# PatchBay.net
KiCad netlist of a schematic drawn in EAGLE
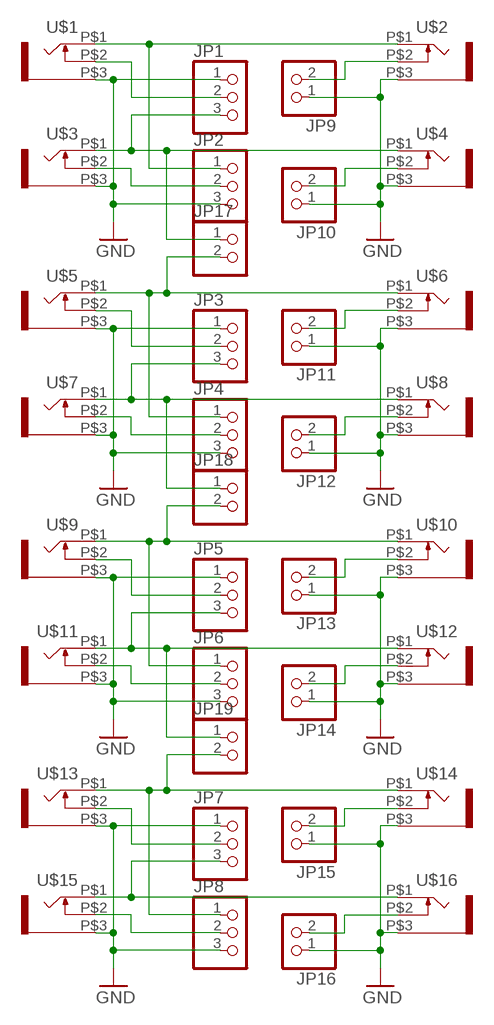
[diagram p0: schematic, sheet 1]

(export (version "E")
  (design (tool "Eeschema 10.0.6"))
  (components
    (comp (ref "JP1")
      (value "PINHD-1X3")
      (footprint "eagle-import:1X03")
      (libsource (lib "eagle-import") (part "PINHD-1X3"))
    )
    (comp (ref "JP2")
      (value "PINHD-1X3")
      (footprint "eagle-import:1X03")
      (libsource (lib "eagle-import") (part "PINHD-1X3"))
    )
    (comp (ref "JP3")
      (value "PINHD-1X3")
      (footprint "eagle-import:1X03")
      (libsource (lib "eagle-import") (part "PINHD-1X3"))
    )
    (comp (ref "JP4")
      (value "PINHD-1X3")
      (footprint "eagle-import:1X03")
      (libsource (lib "eagle-import") (part "PINHD-1X3"))
    )
    (comp (ref "JP5")
      (value "PINHD-1X3")
      (footprint "eagle-import:1X03")
      (libsource (lib "eagle-import") (part "PINHD-1X3"))
    )
    (comp (ref "JP6")
      (value "PINHD-1X3")
      (footprint "eagle-import:1X03")
      (libsource (lib "eagle-import") (part "PINHD-1X3"))
    )
    (comp (ref "JP7")
      (value "PINHD-1X3")
      (footprint "eagle-import:1X03")
      (libsource (lib "eagle-import") (part "PINHD-1X3"))
    )
    (comp (ref "JP8")
      (value "PINHD-1X3")
      (footprint "eagle-import:1X03")
      (libsource (lib "eagle-import") (part "PINHD-1X3"))
    )
    (comp (ref "JP9")
      (value "PINHD-1X2")
      (footprint "eagle-import:1X02")
      (libsource (lib "eagle-import") (part "PINHD-1X2"))
    )
    (comp (ref "JP10")
      (value "PINHD-1X2")
      (footprint "eagle-import:1X02")
      (libsource (lib "eagle-import") (part "PINHD-1X2"))
    )
    (comp (ref "JP11")
      (value "PINHD-1X2")
      (footprint "eagle-import:1X02")
      (libsource (lib "eagle-import") (part "PINHD-1X2"))
    )
    (comp (ref "JP12")
      (value "PINHD-1X2")
      (footprint "eagle-import:1X02")
      (libsource (lib "eagle-import") (part "PINHD-1X2"))
    )
    (comp (ref "JP13")
      (value "PINHD-1X2")
      (footprint "eagle-import:1X02")
      (libsource (lib "eagle-import") (part "PINHD-1X2"))
    )
    (comp (ref "JP14")
      (value "PINHD-1X2")
      (footprint "eagle-import:1X02")
      (libsource (lib "eagle-import") (part "PINHD-1X2"))
    )
    (comp (ref "JP15")
      (value "PINHD-1X2")
      (footprint "eagle-import:1X02")
      (libsource (lib "eagle-import") (part "PINHD-1X2"))
    )
    (comp (ref "JP16")
      (value "PINHD-1X2")
      (footprint "eagle-import:1X02")
      (libsource (lib "eagle-import") (part "PINHD-1X2"))
    )
    (comp (ref "JP17")
      (value "PINHD-1X2")
      (footprint "eagle-import:1X02")
      (libsource (lib "eagle-import") (part "PINHD-1X2"))
    )
    (comp (ref "JP18")
      (value "PINHD-1X2")
      (footprint "eagle-import:1X02")
      (libsource (lib "eagle-import") (part "PINHD-1X2"))
    )
    (comp (ref "JP19")
      (value "PINHD-1X2")
      (footprint "eagle-import:1X02")
      (libsource (lib "eagle-import") (part "PINHD-1X2"))
    )
    (comp (ref "U$1")
      (value "JACK-UJ-3502-R")
      (footprint "eagle-import:UJ-3502-R")
      (libsource (lib "eagle-import") (part "JACK-UJ-3502-R"))
    )
    (comp (ref "U$2")
      (value "JACK-UJ-3502-R")
      (footprint "eagle-import:UJ-3502-R")
      (libsource (lib "eagle-import") (part "JACK-UJ-3502-R"))
    )
    (comp (ref "U$3")
      (value "JACK-UJ-3502-R")
      (footprint "eagle-import:UJ-3502-R")
      (libsource (lib "eagle-import") (part "JACK-UJ-3502-R"))
    )
    (comp (ref "U$4")
      (value "JACK-UJ-3502-R")
      (footprint "eagle-import:UJ-3502-R")
      (libsource (lib "eagle-import") (part "JACK-UJ-3502-R"))
    )
    (comp (ref "U$5")
      (value "JACK-UJ-3502-R")
      (footprint "eagle-import:UJ-3502-R")
      (libsource (lib "eagle-import") (part "JACK-UJ-3502-R"))
    )
    (comp (ref "U$6")
      (value "JACK-UJ-3502-R")
      (footprint "eagle-import:UJ-3502-R")
      (libsource (lib "eagle-import") (part "JACK-UJ-3502-R"))
    )
    (comp (ref "U$7")
      (value "JACK-UJ-3502-R")
      (footprint "eagle-import:UJ-3502-R")
      (libsource (lib "eagle-import") (part "JACK-UJ-3502-R"))
    )
    (comp (ref "U$8")
      (value "JACK-UJ-3502-R")
      (footprint "eagle-import:UJ-3502-R")
      (libsource (lib "eagle-import") (part "JACK-UJ-3502-R"))
    )
    (comp (ref "U$9")
      (value "JACK-UJ-3502-R")
      (footprint "eagle-import:UJ-3502-R")
      (libsource (lib "eagle-import") (part "JACK-UJ-3502-R"))
    )
    (comp (ref "U$10")
      (value "JACK-UJ-3502-R")
      (footprint "eagle-import:UJ-3502-R")
      (libsource (lib "eagle-import") (part "JACK-UJ-3502-R"))
    )
    (comp (ref "U$11")
      (value "JACK-UJ-3502-R")
      (footprint "eagle-import:UJ-3502-R")
      (libsource (lib "eagle-import") (part "JACK-UJ-3502-R"))
    )
    (comp (ref "U$12")
      (value "JACK-UJ-3502-R")
      (footprint "eagle-import:UJ-3502-R")
      (libsource (lib "eagle-import") (part "JACK-UJ-3502-R"))
    )
    (comp (ref "U$13")
      (value "JACK-UJ-3502-R")
      (footprint "eagle-import:UJ-3502-R")
      (libsource (lib "eagle-import") (part "JACK-UJ-3502-R"))
    )
    (comp (ref "U$14")
      (value "JACK-UJ-3502-R")
      (footprint "eagle-import:UJ-3502-R")
      (libsource (lib "eagle-import") (part "JACK-UJ-3502-R"))
    )
    (comp (ref "U$15")
      (value "JACK-UJ-3502-R")
      (footprint "eagle-import:UJ-3502-R")
      (libsource (lib "eagle-import") (part "JACK-UJ-3502-R"))
    )
    (comp (ref "U$16")
      (value "JACK-UJ-3502-R")
      (footprint "eagle-import:UJ-3502-R")
      (libsource (lib "eagle-import") (part "JACK-UJ-3502-R"))
    )
  )
  (nets
    (net (code "1") (name "GND") (class "Default")
      (node (ref "JP1") (pin "1") (pinfunction "1_1") (pintype "passive"))
      (node (ref "JP10") (pin "1") (pinfunction "1_1") (pintype "passive"))
      (node (ref "JP11") (pin "1") (pinfunction "1_1") (pintype "passive"))
      (node (ref "JP12") (pin "1") (pinfunction "1_1") (pintype "passive"))
      (node (ref "JP13") (pin "1") (pinfunction "1_1") (pintype "passive"))
      (node (ref "JP14") (pin "1") (pinfunction "1_1") (pintype "passive"))
      (node (ref "JP15") (pin "1") (pinfunction "1_1") (pintype "passive"))
      (node (ref "JP16") (pin "1") (pinfunction "1_1") (pintype "passive"))
      (node (ref "JP2") (pin "3") (pinfunction "3_3") (pintype "passive"))
      (node (ref "JP3") (pin "1") (pinfunction "1_1") (pintype "passive"))
      (node (ref "JP4") (pin "3") (pinfunction "3_3") (pintype "passive"))
      (node (ref "JP5") (pin "1") (pinfunction "1_1") (pintype "passive"))
      (node (ref "JP6") (pin "3") (pinfunction "3_3") (pintype "passive"))
      (node (ref "JP7") (pin "1") (pinfunction "1_1") (pintype "passive"))
      (node (ref "JP8") (pin "3") (pinfunction "3_3") (pintype "passive"))
      (node (ref "JP9") (pin "1") (pinfunction "1_1") (pintype "passive"))
      (node (ref "U$1") (pin "P$3") (pinfunction "SLEEVE_P$3") (pintype "passive"))
      (node (ref "U$10") (pin "P$3") (pinfunction "SLEEVE_P$3") (pintype "passive"))
      (node (ref "U$11") (pin "P$3") (pinfunction "SLEEVE_P$3") (pintype "passive"))
      (node (ref "U$12") (pin "P$3") (pinfunction "SLEEVE_P$3") (pintype "passive"))
      (node (ref "U$13") (pin "P$3") (pinfunction "SLEEVE_P$3") (pintype "passive"))
      (node (ref "U$14") (pin "P$3") (pinfunction "SLEEVE_P$3") (pintype "passive"))
      (node (ref "U$15") (pin "P$3") (pinfunction "SLEEVE_P$3") (pintype "passive"))
      (node (ref "U$16") (pin "P$3") (pinfunction "SLEEVE_P$3") (pintype "passive"))
      (node (ref "U$2") (pin "P$3") (pinfunction "SLEEVE_P$3") (pintype "passive"))
      (node (ref "U$3") (pin "P$3") (pinfunction "SLEEVE_P$3") (pintype "passive"))
      (node (ref "U$4") (pin "P$3") (pinfunction "SLEEVE_P$3") (pintype "passive"))
      (node (ref "U$5") (pin "P$3") (pinfunction "SLEEVE_P$3") (pintype "passive"))
      (node (ref "U$6") (pin "P$3") (pinfunction "SLEEVE_P$3") (pintype "passive"))
      (node (ref "U$7") (pin "P$3") (pinfunction "SLEEVE_P$3") (pintype "passive"))
      (node (ref "U$8") (pin "P$3") (pinfunction "SLEEVE_P$3") (pintype "passive"))
      (node (ref "U$9") (pin "P$3") (pinfunction "SLEEVE_P$3") (pintype "passive"))
    )
    (net (code "2") (name "Net-(U$1-SW)") (class "Default")
      (node (ref "JP1") (pin "2") (pinfunction "2_2") (pintype "passive"))
      (node (ref "U$1") (pin "P$2") (pinfunction "SW_P$2") (pintype "passive"))
    )
    (net (code "3") (name "Net-(U$1-TIP)") (class "Default")
      (node (ref "JP2") (pin "1") (pinfunction "1_1") (pintype "passive"))
      (node (ref "U$1") (pin "P$1") (pinfunction "TIP_P$1") (pintype "passive"))
      (node (ref "U$2") (pin "P$1") (pinfunction "TIP_P$1") (pintype "passive"))
    )
    (net (code "4") (name "Net-(U$2-SW)") (class "Default")
      (node (ref "JP9") (pin "2") (pinfunction "2_2") (pintype "passive"))
      (node (ref "U$2") (pin "P$2") (pinfunction "SW_P$2") (pintype "passive"))
    )
    (net (code "5") (name "Net-(U$3-SW)") (class "Default")
      (node (ref "JP2") (pin "2") (pinfunction "2_2") (pintype "passive"))
      (node (ref "U$3") (pin "P$2") (pinfunction "SW_P$2") (pintype "passive"))
    )
    (net (code "6") (name "Net-(U$3-TIP)") (class "Default")
      (node (ref "JP1") (pin "3") (pinfunction "3_3") (pintype "passive"))
      (node (ref "JP17") (pin "1") (pinfunction "1_1") (pintype "passive"))
      (node (ref "U$3") (pin "P$1") (pinfunction "TIP_P$1") (pintype "passive"))
      (node (ref "U$4") (pin "P$1") (pinfunction "TIP_P$1") (pintype "passive"))
    )
    (net (code "7") (name "Net-(U$4-SW)") (class "Default")
      (node (ref "JP10") (pin "2") (pinfunction "2_2") (pintype "passive"))
      (node (ref "U$4") (pin "P$2") (pinfunction "SW_P$2") (pintype "passive"))
    )
    (net (code "8") (name "Net-(U$5-SW)") (class "Default")
      (node (ref "JP3") (pin "2") (pinfunction "2_2") (pintype "passive"))
      (node (ref "U$5") (pin "P$2") (pinfunction "SW_P$2") (pintype "passive"))
    )
    (net (code "9") (name "Net-(U$5-TIP)") (class "Default")
      (node (ref "JP17") (pin "2") (pinfunction "2_2") (pintype "passive"))
      (node (ref "JP4") (pin "1") (pinfunction "1_1") (pintype "passive"))
      (node (ref "U$5") (pin "P$1") (pinfunction "TIP_P$1") (pintype "passive"))
      (node (ref "U$6") (pin "P$1") (pinfunction "TIP_P$1") (pintype "passive"))
    )
    (net (code "10") (name "Net-(U$6-SW)") (class "Default")
      (node (ref "JP11") (pin "2") (pinfunction "2_2") (pintype "passive"))
      (node (ref "U$6") (pin "P$2") (pinfunction "SW_P$2") (pintype "passive"))
    )
    (net (code "11") (name "Net-(U$7-SW)") (class "Default")
      (node (ref "JP4") (pin "2") (pinfunction "2_2") (pintype "passive"))
      (node (ref "U$7") (pin "P$2") (pinfunction "SW_P$2") (pintype "passive"))
    )
    (net (code "12") (name "Net-(U$7-TIP)") (class "Default")
      (node (ref "JP18") (pin "1") (pinfunction "1_1") (pintype "passive"))
      (node (ref "JP3") (pin "3") (pinfunction "3_3") (pintype "passive"))
      (node (ref "U$7") (pin "P$1") (pinfunction "TIP_P$1") (pintype "passive"))
      (node (ref "U$8") (pin "P$1") (pinfunction "TIP_P$1") (pintype "passive"))
    )
    (net (code "13") (name "Net-(U$8-SW)") (class "Default")
      (node (ref "JP12") (pin "2") (pinfunction "2_2") (pintype "passive"))
      (node (ref "U$8") (pin "P$2") (pinfunction "SW_P$2") (pintype "passive"))
    )
    (net (code "14") (name "Net-(U$9-SW)") (class "Default")
      (node (ref "JP5") (pin "2") (pinfunction "2_2") (pintype "passive"))
      (node (ref "U$9") (pin "P$2") (pinfunction "SW_P$2") (pintype "passive"))
    )
    (net (code "15") (name "Net-(U$10-SW)") (class "Default")
      (node (ref "JP13") (pin "2") (pinfunction "2_2") (pintype "passive"))
      (node (ref "U$10") (pin "P$2") (pinfunction "SW_P$2") (pintype "passive"))
    )
    (net (code "16") (name "Net-(U$10-TIP)") (class "Default")
      (node (ref "JP18") (pin "2") (pinfunction "2_2") (pintype "passive"))
      (node (ref "JP6") (pin "1") (pinfunction "1_1") (pintype "passive"))
      (node (ref "U$10") (pin "P$1") (pinfunction "TIP_P$1") (pintype "passive"))
      (node (ref "U$9") (pin "P$1") (pinfunction "TIP_P$1") (pintype "passive"))
    )
    (net (code "17") (name "Net-(U$11-SW)") (class "Default")
      (node (ref "JP6") (pin "2") (pinfunction "2_2") (pintype "passive"))
      (node (ref "U$11") (pin "P$2") (pinfunction "SW_P$2") (pintype "passive"))
    )
    (net (code "18") (name "Net-(U$11-TIP)") (class "Default")
      (node (ref "JP19") (pin "1") (pinfunction "1_1") (pintype "passive"))
      (node (ref "JP5") (pin "3") (pinfunction "3_3") (pintype "passive"))
      (node (ref "U$11") (pin "P$1") (pinfunction "TIP_P$1") (pintype "passive"))
      (node (ref "U$12") (pin "P$1") (pinfunction "TIP_P$1") (pintype "passive"))
    )
    (net (code "19") (name "Net-(U$12-SW)") (class "Default")
      (node (ref "JP14") (pin "2") (pinfunction "2_2") (pintype "passive"))
      (node (ref "U$12") (pin "P$2") (pinfunction "SW_P$2") (pintype "passive"))
    )
    (net (code "20") (name "Net-(U$13-SW)") (class "Default")
      (node (ref "JP7") (pin "2") (pinfunction "2_2") (pintype "passive"))
      (node (ref "U$13") (pin "P$2") (pinfunction "SW_P$2") (pintype "passive"))
    )
    (net (code "21") (name "Net-(U$13-TIP)") (class "Default")
      (node (ref "JP19") (pin "2") (pinfunction "2_2") (pintype "passive"))
      (node (ref "JP8") (pin "1") (pinfunction "1_1") (pintype "passive"))
      (node (ref "U$13") (pin "P$1") (pinfunction "TIP_P$1") (pintype "passive"))
      (node (ref "U$14") (pin "P$1") (pinfunction "TIP_P$1") (pintype "passive"))
    )
    (net (code "22") (name "Net-(U$14-SW)") (class "Default")
      (node (ref "JP15") (pin "2") (pinfunction "2_2") (pintype "passive"))
      (node (ref "U$14") (pin "P$2") (pinfunction "SW_P$2") (pintype "passive"))
    )
    (net (code "23") (name "Net-(U$15-SW)") (class "Default")
      (node (ref "JP8") (pin "2") (pinfunction "2_2") (pintype "passive"))
      (node (ref "U$15") (pin "P$2") (pinfunction "SW_P$2") (pintype "passive"))
    )
    (net (code "24") (name "Net-(U$15-TIP)") (class "Default")
      (node (ref "JP7") (pin "3") (pinfunction "3_3") (pintype "passive"))
      (node (ref "U$15") (pin "P$1") (pinfunction "TIP_P$1") (pintype "passive"))
      (node (ref "U$16") (pin "P$1") (pinfunction "TIP_P$1") (pintype "passive"))
    )
    (net (code "25") (name "Net-(U$16-SW)") (class "Default")
      (node (ref "JP16") (pin "2") (pinfunction "2_2") (pintype "passive"))
      (node (ref "U$16") (pin "P$2") (pinfunction "SW_P$2") (pintype "passive"))
    )
  )
)
